# 2_Power.net
KiCad netlist of a schematic drawn in Altium Designer
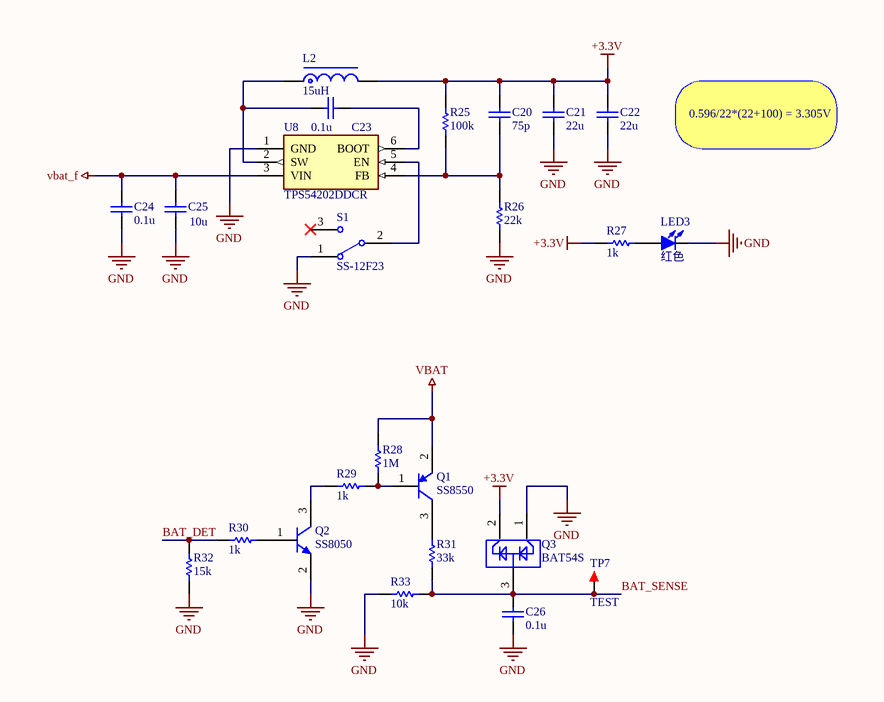
[diagram p0: 2_Power.SchDoc]

(export (version "E")
  (design (tool "Eeschema 10.0.6"))
  (components
    (comp (ref "C20")
      (value "75p")
      (footprint "CAP_0603_SMD")
      (description "Capacitor, 0603, SMD")
      (fields (field (name "PUBLISHER") "Altium Limited"))
      (libsource (lib "myRLC") (part "CAP_0603_SMD"))
    )
    (comp (ref "C21")
      (value "22u")
      (footprint "C1206_L")
      (description "贴片电容")
      (libsource (lib "0.1 - 电阻-电容-电感-电位器") (part "C"))
    )
    (comp (ref "C22")
      (value "22u")
      (footprint "C1206_L")
      (description "贴片电容")
      (libsource (lib "0.1 - 电阻-电容-电感-电位器") (part "C"))
    )
    (comp (ref "C23")
      (value "0.1u")
      (footprint "CAP_0603_SMD")
      (description "Capacitor, 0603, SMD")
      (fields (field (name "PUBLISHER") "Altium Limited"))
      (libsource (lib "myRLC") (part "CAP_0603_SMD"))
    )
    (comp (ref "C24")
      (value "0.1u")
      (footprint "CAP_0603_SMD")
      (description "Capacitor, 0603, SMD")
      (fields (field (name "PUBLISHER") "Altium Limited"))
      (libsource (lib "myRLC") (part "CAP_0603_SMD"))
    )
    (comp (ref "C25")
      (value "10u")
      (footprint "C1206_L")
      (description "贴片电容")
      (libsource (lib "0.1 - 电阻-电容-电感-电位器") (part "C"))
    )
    (comp (ref "C26")
      (value "0.1u")
      (footprint "CAP_0603_SMD")
      (description "Capacitor, 0603, SMD")
      (fields (field (name "PUBLISHER") "Altium Limited"))
      (libsource (lib "myRLC") (part "CAP_0603_SMD"))
    )
    (comp (ref "L2")
      (value "15uH")
      (footprint "L-SMD-0630")
      (description "一体成型电感")
      (libsource (lib "0.1 - 电阻-电容-电感-电位器") (part "L-Molding Choke"))
    )
    (comp (ref "LED3")
      (value "红色")
      (footprint "LED0603_Y")
      (description "贴片LED")
      (libsource (lib "0.3 - LED发光二极管") (part "LED-SMD"))
    )
    (comp (ref "Q1")
      (value "SS8550")
      (footprint "TR_SOT-23")
      (description "PNP SS8550, -25V -1.5A, SOT-23")
      (fields (field (name "PUBLISHER") "Altium Limited"))
      (libsource (lib "myTransistors&Diodes") (part "PNP SS8550"))
    )
    (comp (ref "Q2")
      (value "SS8050")
      (footprint "TR_SOT-23")
      (description "NPN SS8050, 25V 1.5A, SOT-23")
      (fields (field (name "PUBLISHER") "Altium Limited"))
      (libsource (lib "myTransistors&Diodes") (part "NPN SS8050"))
    )
    (comp (ref "Q3")
      (value "BAT54S")
      (footprint "TR_SOT-23")
      (description "Dual Schottky Diodes, SOT23")
      (libsource (lib "myTransistors&Diodes") (part "BAT54S"))
    )
    (comp (ref "R25")
      (value "100k")
      (footprint "RES_0603_SMD")
      (description "Resistor, 0603, SMD")
      (fields (field (name "PUBLISHER") "Altium Limited"))
      (libsource (lib "myRLC") (part "RES_0603_SMD"))
    )
    (comp (ref "R26")
      (value "22k")
      (footprint "RES_0603_SMD")
      (description "Resistor, 0603, SMD")
      (fields (field (name "PUBLISHER") "Altium Limited"))
      (libsource (lib "myRLC") (part "RES_0603_SMD"))
    )
    (comp (ref "R27")
      (value "1k")
      (footprint "RES_0603_SMD")
      (description "Resistor, 0603, SMD")
      (fields (field (name "PUBLISHER") "Altium Limited"))
      (libsource (lib "myRLC") (part "RES_0603_SMD"))
    )
    (comp (ref "R28")
      (value "1M")
      (footprint "RES_0603_SMD")
      (description "Resistor, 0603, SMD")
      (fields (field (name "PUBLISHER") "Altium Limited"))
      (libsource (lib "myRLC") (part "RES_0603_SMD"))
    )
    (comp (ref "R29")
      (value "1k")
      (footprint "RES_0603_SMD")
      (description "Resistor, 0603, SMD")
      (fields (field (name "PUBLISHER") "Altium Limited"))
      (libsource (lib "myRLC") (part "RES_0603_SMD"))
    )
    (comp (ref "R30")
      (value "1k")
      (footprint "RES_0603_SMD")
      (description "Resistor, 0603, SMD")
      (fields (field (name "PUBLISHER") "Altium Limited"))
      (libsource (lib "myRLC") (part "RES_0603_SMD"))
    )
    (comp (ref "R31")
      (value "33k")
      (footprint "RES_0603_SMD")
      (description "Resistor, 0603, SMD")
      (fields (field (name "PUBLISHER") "Altium Limited"))
      (libsource (lib "myRLC") (part "RES_0603_SMD"))
    )
    (comp (ref "R32")
      (value "15k")
      (footprint "RES_0603_SMD")
      (description "Resistor, 0603, SMD")
      (fields (field (name "PUBLISHER") "Altium Limited"))
      (libsource (lib "myRLC") (part "RES_0603_SMD"))
    )
    (comp (ref "R33")
      (value "10k")
      (footprint "RES_0603_SMD")
      (description "Resistor, 0603, SMD")
      (fields (field (name "PUBLISHER") "Altium Limited"))
      (libsource (lib "myRLC") (part "RES_0603_SMD"))
    )
    (comp (ref "S1")
      (value "SS-12F23")
      (footprint "SS-12F23")
      (description "1路波动开关")
      (libsource (lib "0.7 - 常用按键-开关-蜂鸣器-电池-测试点") (part "SSW-1P"))
    )
    (comp (ref "TP7")
      (value "TEST")
      (footprint "TEST 1.2")
      (description "测试点")
      (libsource (lib "0.7 - 常用按键-开关-蜂鸣器-电池-测试点") (part "TEST"))
    )
    (comp (ref "U8")
      (value "TPS54202DDCR")
      (footprint "TKY:SOT95P280X110-6N")
      (description "Power Supply")
      (fields (field (name "MOUSER PART NUMBER") "595-TPS54202DDCR"))
      (libsource (lib "TKY") (part "TPS54202DDCR"))
    )
  )
  (nets
    (net (code "1") (name "+3.3V") (class "Default")
      (node (ref "C20") (pin "1") (pinfunction "1_1") (pintype "passive"))
      (node (ref "C21") (pin "2") (pinfunction "2_2") (pintype "passive"))
      (node (ref "C22") (pin "2") (pinfunction "2_2") (pintype "passive"))
      (node (ref "L2") (pin "2") (pinfunction "2_2") (pintype "passive"))
      (node (ref "Q3") (pin "2") (pinfunction "2_2") (pintype "passive"))
      (node (ref "R25") (pin "2") (pinfunction "2_2") (pintype "passive"))
      (node (ref "R27") (pin "2") (pinfunction "2_2") (pintype "passive"))
    )
    (net (code "2") (name "/BAT_DET") (class "Default")
      (node (ref "R30") (pin "1") (pinfunction "1_1") (pintype "passive"))
      (node (ref "R32") (pin "2") (pinfunction "2_2") (pintype "passive"))
    )
    (net (code "3") (name "/BAT_SENSE") (class "Default")
      (node (ref "C26") (pin "2") (pinfunction "2_2") (pintype "passive"))
      (node (ref "Q3") (pin "3") (pinfunction "3_3") (pintype "passive"))
      (node (ref "R31") (pin "2") (pinfunction "2_2") (pintype "passive"))
      (node (ref "R33") (pin "2") (pinfunction "2_2") (pintype "passive"))
      (node (ref "TP7") (pin "1") (pinfunction "1_1") (pintype "passive"))
    )
    (net (code "4") (name "GND") (class "Default")
      (node (ref "C21") (pin "1") (pinfunction "1_1") (pintype "passive"))
      (node (ref "C22") (pin "1") (pinfunction "1_1") (pintype "passive"))
      (node (ref "C24") (pin "1") (pinfunction "1_1") (pintype "passive"))
      (node (ref "C25") (pin "1") (pinfunction "1_1") (pintype "passive"))
      (node (ref "C26") (pin "1") (pinfunction "1_1") (pintype "passive"))
      (node (ref "LED3") (pin "2") (pinfunction "K_2") (pintype "passive"))
      (node (ref "Q2") (pin "2") (pinfunction "E_2") (pintype "passive"))
      (node (ref "Q3") (pin "1") (pinfunction "1_1") (pintype "passive"))
      (node (ref "R26") (pin "1") (pinfunction "1_1") (pintype "passive"))
      (node (ref "R32") (pin "1") (pinfunction "1_1") (pintype "passive"))
      (node (ref "R33") (pin "1") (pinfunction "1_1") (pintype "passive"))
      (node (ref "S1") (pin "1") (pinfunction "1_1") (pintype "passive"))
      (node (ref "U8") (pin "1") (pinfunction "GND_1") (pintype "power_in"))
    )
    (net (code "5") (name "Net-(LED3-A)") (class "Default")
      (node (ref "LED3") (pin "1") (pinfunction "A_1") (pintype "passive"))
      (node (ref "R27") (pin "1") (pinfunction "1_1") (pintype "passive"))
    )
    (net (code "6") (name "Net-(Q1-B)") (class "Default")
      (node (ref "Q1") (pin "1") (pinfunction "B_1") (pintype "passive"))
      (node (ref "R28") (pin "1") (pinfunction "1_1") (pintype "passive"))
      (node (ref "R29") (pin "1") (pinfunction "1_1") (pintype "passive"))
    )
    (net (code "7") (name "Net-(Q1-C)") (class "Default")
      (node (ref "Q1") (pin "3") (pinfunction "C_3") (pintype "passive"))
      (node (ref "R31") (pin "1") (pinfunction "1_1") (pintype "passive"))
    )
    (net (code "8") (name "Net-(Q2-B)") (class "Default")
      (node (ref "Q2") (pin "1") (pinfunction "B_1") (pintype "passive"))
      (node (ref "R30") (pin "2") (pinfunction "2_2") (pintype "passive"))
    )
    (net (code "9") (name "Net-(Q2-C)") (class "Default")
      (node (ref "Q2") (pin "3") (pinfunction "C_3") (pintype "passive"))
      (node (ref "R29") (pin "2") (pinfunction "2_2") (pintype "passive"))
    )
    (net (code "10") (name "Net-(U8-BOOT)") (class "Default")
      (node (ref "C23") (pin "1") (pinfunction "1_1") (pintype "passive"))
      (node (ref "U8") (pin "6") (pinfunction "BOOT_6") (pintype "output"))
    )
    (net (code "11") (name "Net-(U8-EN)") (class "Default")
      (node (ref "S1") (pin "2") (pinfunction "2_2") (pintype "passive"))
      (node (ref "U8") (pin "5") (pinfunction "EN_5") (pintype "input"))
    )
    (net (code "12") (name "Net-(U8-FB)") (class "Default")
      (node (ref "C20") (pin "2") (pinfunction "2_2") (pintype "passive"))
      (node (ref "R25") (pin "1") (pinfunction "1_1") (pintype "passive"))
      (node (ref "R26") (pin "2") (pinfunction "2_2") (pintype "passive"))
      (node (ref "U8") (pin "4") (pinfunction "FB_4") (pintype "input"))
    )
    (net (code "13") (name "Net-(U8-SW)") (class "Default")
      (node (ref "C23") (pin "2") (pinfunction "2_2") (pintype "passive"))
      (node (ref "L2") (pin "1") (pinfunction "1_1") (pintype "passive"))
      (node (ref "U8") (pin "2") (pinfunction "SW_2") (pintype "output"))
    )
    (net (code "14") (name "VBAT") (class "Default")
      (node (ref "Q1") (pin "2") (pinfunction "E_2") (pintype "passive"))
      (node (ref "R28") (pin "2") (pinfunction "2_2") (pintype "passive"))
    )
    (net (code "15") (name "unconnected-(S1-Pad3)") (class "Default")
      (node (ref "S1") (pin "3") (pinfunction "3_3") (pintype "passive+no_connect"))
    )
    (net (code "16") (name "vbat_f") (class "Default")
      (node (ref "C24") (pin "2") (pinfunction "2_2") (pintype "passive"))
      (node (ref "C25") (pin "2") (pinfunction "2_2") (pintype "passive"))
      (node (ref "U8") (pin "3") (pinfunction "VIN_3") (pintype "power_in"))
    )
  )
)
